# SR_Latch.net
KiCad netlist of a schematic drawn in Altium Designer
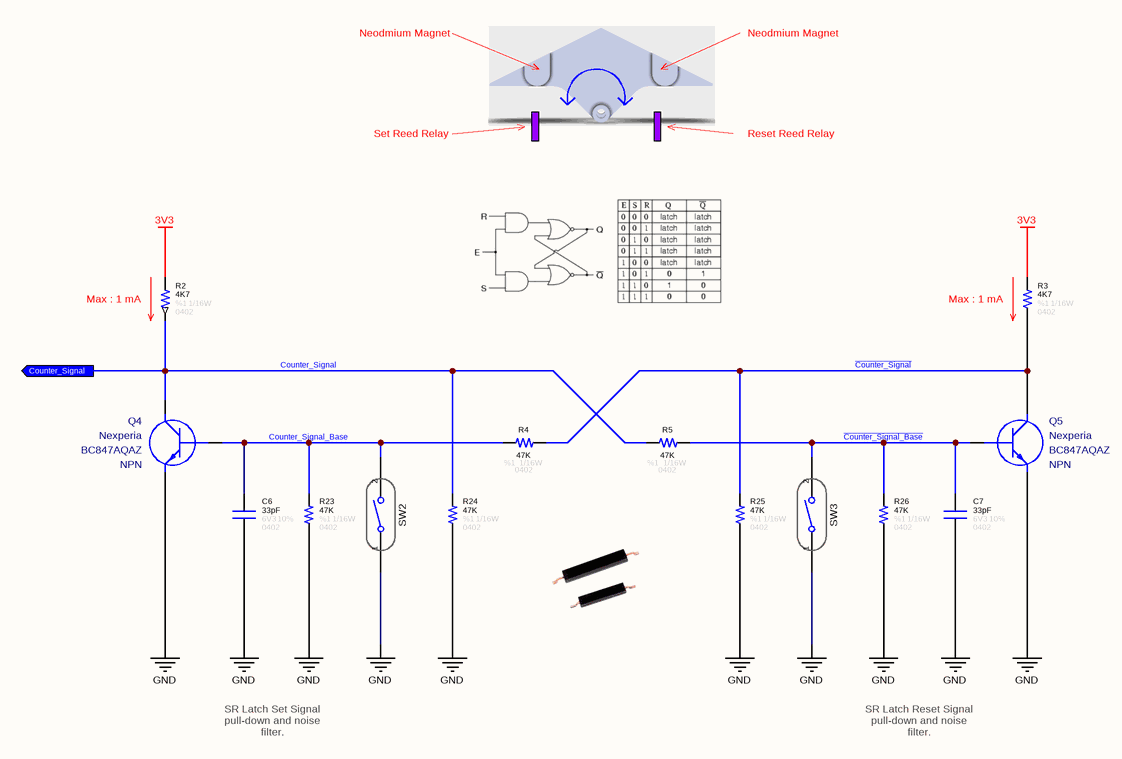
[diagram p0: SR Latch.SchDoc]

(export (version "E")
  (design (tool "Eeschema 10.0.6"))
  (components
    (comp (ref "C6")
      (value "33pF")
      (footprint "CAPACITOR_0402")
      (description "Capacitor - 33pF [0402] (Ceramic)")
      (fields
        (field (name "MANUFACTURER PART NUMBER") "C0402C330J9RACAUTO")
        (field (name "TOLERANCE") "10%")
        (field (name "CASE") "0402")
        (field (name "VOLTAGE") "6V3")
      )
      (libsource (lib "Akkoyun") (part "Capacitor - 33pF [0402-6V3]"))
    )
    (comp (ref "C7")
      (value "33pF")
      (footprint "CAPACITOR_0402")
      (description "Capacitor - 33pF [0402] (Ceramic)")
      (fields
        (field (name "MANUFACTURER PART NUMBER") "C0402C330J9RACAUTO")
        (field (name "TOLERANCE") "10%")
        (field (name "CASE") "0402")
        (field (name "VOLTAGE") "6V3")
      )
      (libsource (lib "Akkoyun") (part "Capacitor - 33pF [0402-6V3]"))
    )
    (comp (ref "Q4")
      (value "~")
      (footprint "SOT1215")
      (description "Bipolar NPN Transistors")
      (fields
        (field (name "MANUFACTURER NAME") "Nexperia")
        (field (name "MANUFACTURER PART NUMBER") "BC847AQAZ")
        (field (name "POLARITY") "NPN")
      )
      (libsource (lib "Akkoyun") (part "Transistor - BC847"))
    )
    (comp (ref "Q5")
      (value "~")
      (footprint "SOT1215")
      (description "Bipolar NPN Transistors")
      (fields
        (field (name "MANUFACTURER NAME") "Nexperia")
        (field (name "MANUFACTURER PART NUMBER") "BC847AQAZ")
        (field (name "POLARITY") "NPN")
      )
      (libsource (lib "Akkoyun") (part "Transistor - BC847"))
    )
    (comp (ref "R2")
      (value "4K7")
      (footprint "RESISTOR_0402")
      (description "Thick Film Resistors - SMD 1/16 W 4.7 KOhm 1%")
      (fields
        (field (name "MANUFACTURER PART NUMBER") "CRCW04024K70FKED")
        (field (name "TOLERANCE") "%1")
        (field (name "CASE") "0402")
        (field (name "POWER") "1/16W")
      )
      (libsource (lib "Akkoyun") (part "Resistor - 4K7 [0402]"))
    )
    (comp (ref "R3")
      (value "4K7")
      (footprint "RESISTOR_0402")
      (description "Thick Film Resistors - SMD 1/16 W 4.7 KOhm 1%")
      (fields
        (field (name "MANUFACTURER PART NUMBER") "CRCW04024K70FKED")
        (field (name "TOLERANCE") "%1")
        (field (name "CASE") "0402")
        (field (name "POWER") "1/16W")
      )
      (libsource (lib "Akkoyun") (part "Resistor - 4K7 [0402]"))
    )
    (comp (ref "R4")
      (value "47K")
      (footprint "RESISTOR_0402")
      (description "Thick Film Resistors - SMD 1/16 W 47 KOhm 1%")
      (fields
        (field (name "MANUFACTURER PART NUMBER") "CRCW040247K0FKED")
        (field (name "TOLERANCE") "%1")
        (field (name "CASE") "0402")
        (field (name "POWER") "1/16W")
      )
      (libsource (lib "Akkoyun") (part "Resistor - 47K [0402]"))
    )
    (comp (ref "R5")
      (value "47K")
      (footprint "RESISTOR_0402")
      (description "Thick Film Resistors - SMD 1/16 W 47 KOhm 1%")
      (fields
        (field (name "MANUFACTURER PART NUMBER") "CRCW040247K0FKED")
        (field (name "TOLERANCE") "%1")
        (field (name "CASE") "0402")
        (field (name "POWER") "1/16W")
      )
      (libsource (lib "Akkoyun") (part "Resistor - 47K [0402]"))
    )
    (comp (ref "R23")
      (value "47K")
      (footprint "RESISTOR_0402")
      (description "Thick Film Resistors - SMD 1/16 W 47 KOhm 1%")
      (fields
        (field (name "MANUFACTURER PART NUMBER") "CRCW040247K0FKED")
        (field (name "TOLERANCE") "%1")
        (field (name "CASE") "0402")
        (field (name "POWER") "1/16W")
      )
      (libsource (lib "Akkoyun") (part "Resistor - 47K [0402]"))
    )
    (comp (ref "R24")
      (value "47K")
      (footprint "RESISTOR_0402")
      (description "Thick Film Resistors - SMD 1/16 W 47 KOhm 1%")
      (fields
        (field (name "MANUFACTURER PART NUMBER") "CRCW040247K0FKED")
        (field (name "TOLERANCE") "%1")
        (field (name "CASE") "0402")
        (field (name "POWER") "1/16W")
      )
      (libsource (lib "Akkoyun") (part "Resistor - 47K [0402]"))
    )
    (comp (ref "R25")
      (value "47K")
      (footprint "RESISTOR_0402")
      (description "Thick Film Resistors - SMD 1/16 W 47 KOhm 1%")
      (fields
        (field (name "MANUFACTURER PART NUMBER") "CRCW040247K0FKED")
        (field (name "TOLERANCE") "%1")
        (field (name "CASE") "0402")
        (field (name "POWER") "1/16W")
      )
      (libsource (lib "Akkoyun") (part "Resistor - 47K [0402]"))
    )
    (comp (ref "R26")
      (value "47K")
      (footprint "RESISTOR_0402")
      (description "Thick Film Resistors - SMD 1/16 W 47 KOhm 1%")
      (fields
        (field (name "MANUFACTURER PART NUMBER") "CRCW040247K0FKED")
        (field (name "TOLERANCE") "%1")
        (field (name "CASE") "0402")
        (field (name "POWER") "1/16W")
      )
      (libsource (lib "Akkoyun") (part "Resistor - 47K [0402]"))
    )
    (comp (ref "SW2")
      (value "~")
      (footprint "REED Relay")
      (description "Reed relay - SMD 11.7 mm")
      (fields (field (name "MANUFACTURER PART NUMBER") "MKA-10110MS"))
      (libsource (lib "Akkoyun") (part "Switch - Reed Relay"))
    )
    (comp (ref "SW3")
      (value "~")
      (footprint "REED Relay")
      (description "Reed relay - SMD 11.7 mm")
      (fields (field (name "MANUFACTURER PART NUMBER") "MKA-10110MS"))
      (libsource (lib "Akkoyun") (part "Switch - Reed Relay"))
    )
  )
  (nets
    (net (code "1") (name "/Counter_Signal") (class "Default")
      (node (ref "Q4") (pin "3") (pinfunction "C_3") (pintype "passive"))
      (node (ref "R2") (pin "1") (pinfunction "1_1") (pintype "output"))
      (node (ref "R24") (pin "2") (pinfunction "2_2") (pintype "passive"))
      (node (ref "R5") (pin "2") (pinfunction "2_2") (pintype "passive"))
    )
    (net (code "2") (name "/Counter_Signal_Base") (class "Default")
      (node (ref "C6") (pin "2") (pinfunction "2_2") (pintype "passive"))
      (node (ref "Q4") (pin "1") (pinfunction "B_1") (pintype "passive"))
      (node (ref "R23") (pin "2") (pinfunction "2_2") (pintype "passive"))
      (node (ref "R4") (pin "2") (pinfunction "2_2") (pintype "passive"))
      (node (ref "SW2") (pin "2") (pinfunction "COM_2") (pintype "passive"))
    )
    (net (code "3") (name "/~{Counter_Signal_Base}") (class "Default")
      (node (ref "C7") (pin "2") (pinfunction "2_2") (pintype "passive"))
      (node (ref "Q5") (pin "1") (pinfunction "B_1") (pintype "passive"))
      (node (ref "R26") (pin "2") (pinfunction "2_2") (pintype "passive"))
      (node (ref "R5") (pin "1") (pinfunction "1_1") (pintype "passive"))
      (node (ref "SW3") (pin "2") (pinfunction "COM_2") (pintype "passive"))
    )
    (net (code "4") (name "/~{Counter_Signal}") (class "Default")
      (node (ref "Q5") (pin "3") (pinfunction "C_3") (pintype "passive"))
      (node (ref "R25") (pin "2") (pinfunction "2_2") (pintype "passive"))
      (node (ref "R3") (pin "1") (pinfunction "1_1") (pintype "output"))
      (node (ref "R4") (pin "1") (pinfunction "1_1") (pintype "passive"))
    )
    (net (code "5") (name "3V3") (class "Default")
      (node (ref "R2") (pin "2") (pinfunction "2_2") (pintype "passive"))
      (node (ref "R3") (pin "2") (pinfunction "2_2") (pintype "passive"))
    )
    (net (code "6") (name "GND") (class "Default")
      (node (ref "C6") (pin "1") (pinfunction "1_1") (pintype "passive"))
      (node (ref "C7") (pin "1") (pinfunction "1_1") (pintype "passive"))
      (node (ref "Q4") (pin "2") (pinfunction "E_2") (pintype "passive"))
      (node (ref "Q5") (pin "2") (pinfunction "E_2") (pintype "passive"))
      (node (ref "R23") (pin "1") (pinfunction "1_1") (pintype "passive"))
      (node (ref "R24") (pin "1") (pinfunction "1_1") (pintype "passive"))
      (node (ref "R25") (pin "1") (pinfunction "1_1") (pintype "passive"))
      (node (ref "R26") (pin "1") (pinfunction "1_1") (pintype "passive"))
      (node (ref "SW2") (pin "1") (pinfunction "NC_1") (pintype "passive"))
      (node (ref "SW3") (pin "1") (pinfunction "NC_1") (pintype "passive"))
    )
  )
)
